# AIn_Isolator.net
KiCad netlist of a schematic drawn in Altium Designer
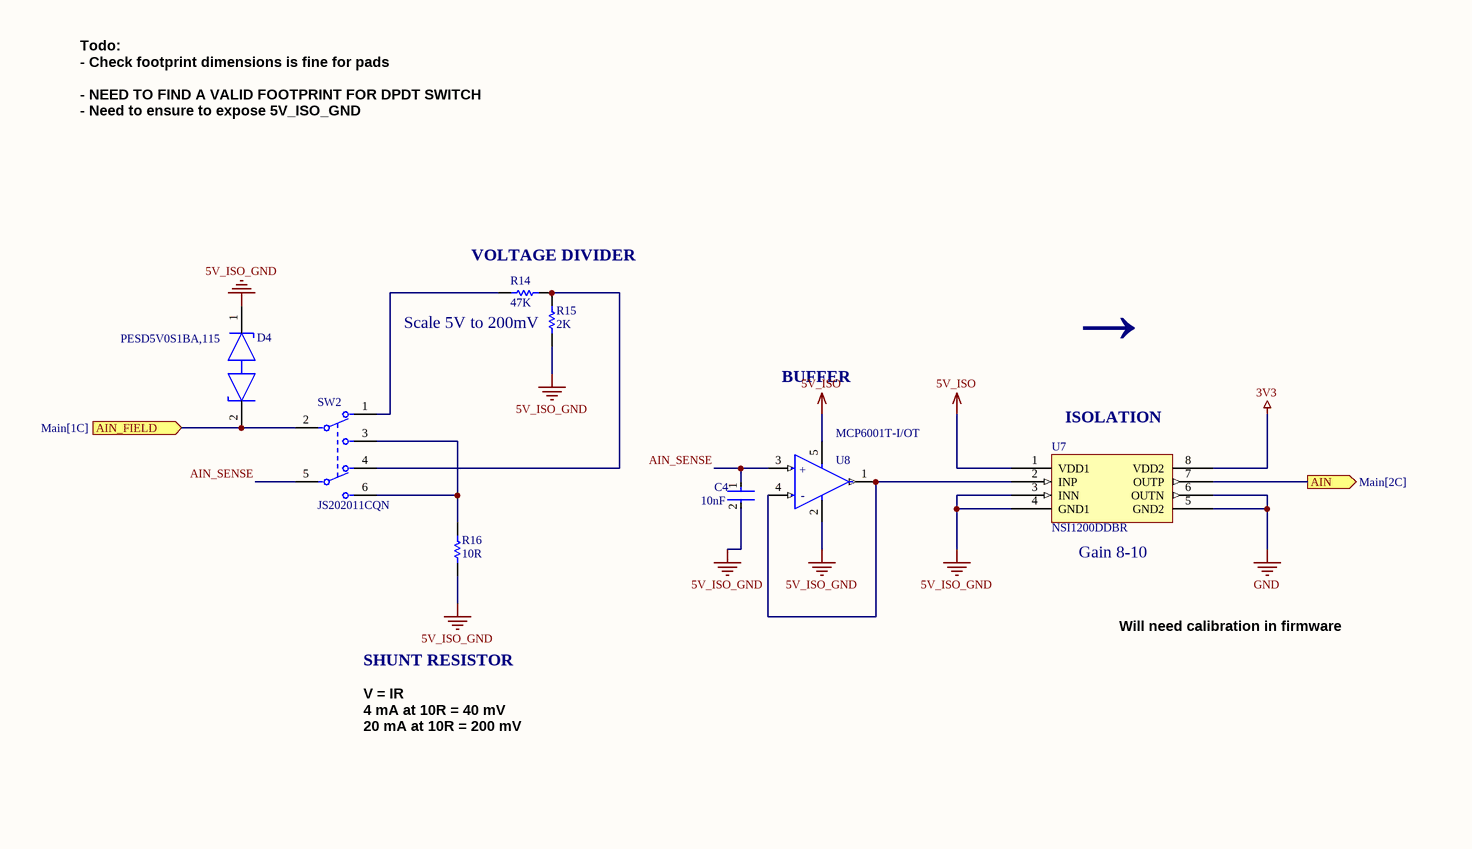
[diagram p0: AIn_Isolator.SchDoc, left]
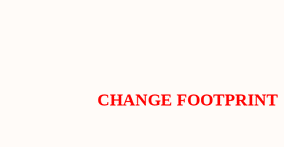
[diagram p1: AIn_Isolator.SchDoc, right]

(export (version "E")
  (design (tool "Eeschema 10.0.6"))
  (components
    (comp (ref "C4")
      (value "10nF")
      (footprint "FP-CC0603-DA-MFG")
      (description "CAP CER 10000PF 50V X7R 0603")
      (fields (field (name "TOLERANCE") "0.1") (field (name "MANUFACTURER PART NUMBER") "CC0603KRX7R9BB103"))
      (libsource (lib "Altium Content Vault") (part "11868f565c42a9108669ba33697ecf6"))
    )
    (comp (ref "D4")
      (value "PESD5V0S1BA,115")
      (footprint "FP-SOD323-CA-MFG")
      (description "TVS DIODE 5V 14V SOD323")
      (libsource (lib "Altium Content Vault") (part "f6dbb2535d6b2d347ec798cb4d032a4"))
    )
    (comp (ref "R14")
      (value "47K")
      (footprint "RESC1608X55X30NL15T15")
      (description "Chip Resistor, 47 KOhm, +/- 1%, 0.1 W, -55 to 155 degC, 0603 (1608 Metric), RoHS, Tape and Reel")
      (libsource (lib "Altium Content Vault") (part "RES-2"))
    )
    (comp (ref "R15")
      (value "2K")
      (footprint "RESC1608X55X30ML15T15")
      (fields (field (name "PART NUMBER") "ERJ-3EKF2001V") (field (name "MANUFACTURER") "Panasonic"))
      (libsource (lib "Altium Content Vault") (part "RES"))
    )
    (comp (ref "R16")
      (value "10R")
      (footprint "RESC3216X70X50LL20T25")
      (fields (field (name "MANUFACTURER") "Panasonic") (field (name "PART NUMBER") "ERA8AEB103V"))
      (libsource (lib "Altium Content Vault") (part "RES"))
    )
    (comp (ref "SW2")
      (value "JS202011CQN")
      (footprint "FP-JS202011CQN-MFG - duplicate")
      (description "SWITCH SLIDE DPDT 300MA 6V")
      (libsource (lib "JS202011CQN ") (part "CMP-10038-000022-1_1"))
    )
    (comp (ref "U7")
      (value "NSI1200DDBR")
      (footprint "NSI1200DDBR")
      (description "High Reliability Reinforced Isolated Amplifier")
      (fields (field (name "MANUFACTURER") "Novosense"))
      (libsource (lib "nsi1200") (part "NSI1200DDBR"))
    )
    (comp (ref "U8")
      (value "MCP6001T-I/OT")
      (footprint "FP-C04-091-OT-IPC_A")
      (description "IC OPAMP GP 1 CIRCUIT SOT23-5")
      (fields (field (name "VOLTAGE") "6V"))
      (libsource (lib "Altium Content Vault") (part "c8a8c153b9e84e05c1733c8ea85bdd9"))
    )
  )
  (nets
    (net (code "1") (name "/AIN") (class "Default")
      (node (ref "U7") (pin "7") (pinfunction "OUTP_7") (pintype "output"))
    )
    (net (code "2") (name "/AIN_FIELD") (class "Default")
      (node (ref "D4") (pin "2") (pinfunction "K2_2") (pintype "passive"))
      (node (ref "SW2") (pin "2") (pinfunction "2_2") (pintype "passive"))
    )
    (net (code "3") (name "/AIN_SENSE") (class "Default")
      (node (ref "C4") (pin "1") (pinfunction "1_1") (pintype "passive"))
      (node (ref "SW2") (pin "5") (pinfunction "5_5") (pintype "passive"))
      (node (ref "U8") (pin "3") (pinfunction "VIN+_3") (pintype "input"))
    )
    (net (code "4") (name "3V3") (class "Default")
      (node (ref "U7") (pin "8") (pinfunction "VDD2_8") (pintype "power_in"))
    )
    (net (code "5") (name "5V_ISO") (class "Default")
      (node (ref "U7") (pin "1") (pinfunction "VDD1_1") (pintype "power_in"))
      (node (ref "U8") (pin "5") (pinfunction "VDD_5") (pintype "power_in"))
    )
    (net (code "6") (name "5V_ISO_GND") (class "Default")
      (node (ref "C4") (pin "2") (pinfunction "2_2") (pintype "passive"))
      (node (ref "D4") (pin "1") (pinfunction "K1_1") (pintype "passive"))
      (node (ref "R15") (pin "1") (pinfunction "1_1") (pintype "passive"))
      (node (ref "R16") (pin "2") (pinfunction "2_2") (pintype "passive"))
      (node (ref "U7") (pin "3") (pinfunction "INN_3") (pintype "input"))
      (node (ref "U7") (pin "4") (pinfunction "GND1_4") (pintype "power_in"))
      (node (ref "U8") (pin "2") (pinfunction "VSS_2") (pintype "power_in"))
    )
    (net (code "7") (name "GND") (class "Default")
      (node (ref "U7") (pin "5") (pinfunction "GND2_5") (pintype "power_in"))
      (node (ref "U7") (pin "6") (pinfunction "OUTN_6") (pintype "output"))
    )
    (net (code "8") (name "Net-(R14-Pad1)") (class "Default")
      (node (ref "R14") (pin "1") (pinfunction "1_1") (pintype "passive"))
      (node (ref "SW2") (pin "1") (pinfunction "1_1") (pintype "passive"))
    )
    (net (code "9") (name "Net-(R14-Pad2)") (class "Default")
      (node (ref "R14") (pin "2") (pinfunction "2_2") (pintype "passive"))
      (node (ref "R15") (pin "2") (pinfunction "2_2") (pintype "passive"))
      (node (ref "SW2") (pin "4") (pinfunction "4_4") (pintype "passive"))
    )
    (net (code "10") (name "Net-(R16-Pad1)") (class "Default")
      (node (ref "R16") (pin "1") (pinfunction "1_1") (pintype "passive"))
      (node (ref "SW2") (pin "3") (pinfunction "3_3") (pintype "passive"))
      (node (ref "SW2") (pin "6") (pinfunction "6_6") (pintype "passive"))
    )
    (net (code "11") (name "Net-(U7-INP)") (class "Default")
      (node (ref "U7") (pin "2") (pinfunction "INP_2") (pintype "input"))
      (node (ref "U8") (pin "1") (pinfunction "VOUT_1") (pintype "output"))
      (node (ref "U8") (pin "4") (pinfunction "VIN-_4") (pintype "input"))
    )
  )
)
